# Arduino_BNO080.net
KiCad netlist of a schematic drawn in EAGLE
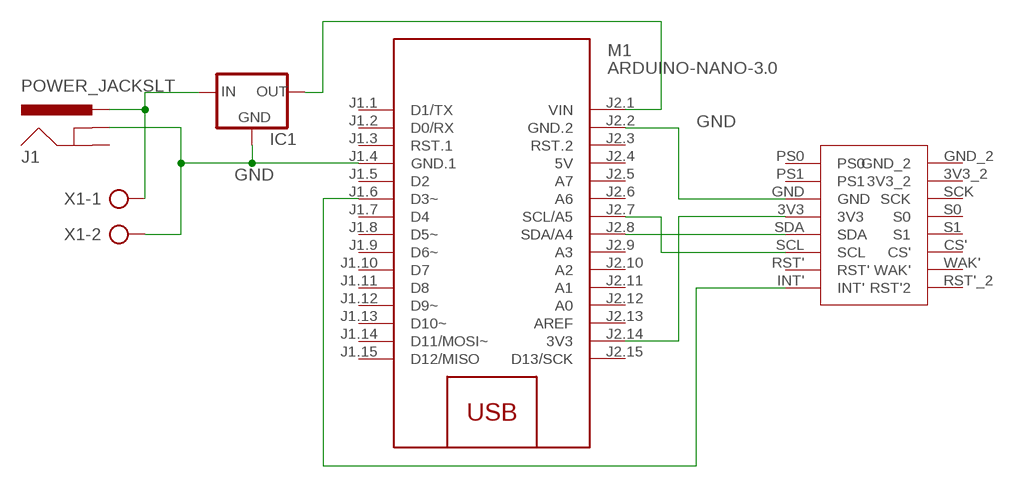
[diagram p0: schematic, sheet 1]

(export (version "E")
  (design (tool "Eeschema 10.0.6"))
  (components
    (comp (ref "IC1")
      (value "78XXS")
      (footprint "eagle-import:78XXS")
      (libsource (lib "eagle-import") (part "78XXS"))
    )
    (comp (ref "J1")
      (value "POWER_JACKSLT")
      (footprint "eagle-import:POWER_JACK_SLOT")
      (libsource (lib "eagle-import") (part "POWER_JACKSLT"))
    )
    (comp (ref "M1")
      (value "ARDUINO-NANO-3.0")
      (footprint "eagle-import:ARDUINO-NANO-3.0")
      (libsource (lib "eagle-import") (part "ARDUINO-NANO-3.0"))
    )
    (comp (ref "U$1")
      (value "BNO080")
      (footprint "eagle-import:BNO080")
      (libsource (lib "eagle-import") (part "BNO080"))
    )
    (comp (ref "X1")
      (value "AK300/2")
      (footprint "eagle-import:AK300_2")
      (libsource (lib "eagle-import") (part "AK300/2"))
    )
  )
  (nets
    (net (code "1") (name "/5V") (class "Default")
      (node (ref "M1") (pin "J2.4") (pinfunction "5V_J2.4") (pintype "power_in"))
    )
    (net (code "2") (name "/GND") (class "Default")
      (node (ref "IC1") (pin "GND") (pinfunction "GND_GND") (pintype "input"))
      (node (ref "J1") (pin "GND@1") (pinfunction "GNDBREAK_GND@1") (pintype "bidirectional"))
      (node (ref "M1") (pin "J1.4") (pinfunction "GND.1_J1.4") (pintype "power_in"))
      (node (ref "M1") (pin "J2.2") (pinfunction "GND.2_J2.2") (pintype "power_in"))
      (node (ref "U$1") (pin "GND") (pinfunction "GND_GND") (pintype "bidirectional"))
      (node (ref "X1") (pin "2") (pinfunction "KL_2") (pintype "passive"))
    )
    (net (code "3") (name "Net-(M1-3V3)") (class "Default")
      (node (ref "M1") (pin "J2.14") (pinfunction "3V3_J2.14") (pintype "power_in"))
      (node (ref "U$1") (pin "3V3") (pinfunction "3V3_3V3") (pintype "bidirectional"))
    )
    (net (code "4") (name "Net-(M1-D3~{})") (class "Default")
      (node (ref "M1") (pin "J1.6") (pinfunction "D3~{}_J1.6") (pintype "bidirectional"))
      (node (ref "U$1") (pin "INT'") (pinfunction "INT'_INT'") (pintype "bidirectional"))
    )
    (net (code "5") (name "Net-(M1-SCL{slash}A5)") (class "Default")
      (node (ref "M1") (pin "J2.7") (pinfunction "SCL/A5_J2.7") (pintype "bidirectional"))
      (node (ref "U$1") (pin "SCL") (pinfunction "SCL_SCL") (pintype "bidirectional"))
    )
    (net (code "6") (name "Net-(M1-SDA{slash}A4)") (class "Default")
      (node (ref "M1") (pin "J2.8") (pinfunction "SDA/A4_J2.8") (pintype "bidirectional"))
      (node (ref "U$1") (pin "SDA") (pinfunction "SDA_SDA") (pintype "bidirectional"))
    )
    (net (code "7") (name "Net-(M1-VIN)") (class "Default")
      (node (ref "IC1") (pin "OUT") (pinfunction "OUT_OUT") (pintype "passive"))
      (node (ref "M1") (pin "J2.1") (pinfunction "VIN_J2.1") (pintype "power_in"))
    )
    (net (code "8") (name "Net-(X1A-KL)") (class "Default")
      (node (ref "IC1") (pin "IN") (pinfunction "IN_IN") (pintype "input"))
      (node (ref "J1") (pin "PWR") (pinfunction "PWR_PWR") (pintype "bidirectional"))
      (node (ref "X1") (pin "1") (pinfunction "KL_1") (pintype "passive"))
    )
    (net (code "9") (name "unconnected-(J1-GND-PadGND@2)") (class "Default")
      (node (ref "J1") (pin "GND@2") (pinfunction "GND_GND@2") (pintype "bidirectional"))
    )
    (net (code "10") (name "unconnected-(M1-A0-PadJ2.12)") (class "Default")
      (node (ref "M1") (pin "J2.12") (pinfunction "A0_J2.12") (pintype "bidirectional"))
    )
    (net (code "11") (name "unconnected-(M1-A1-PadJ2.11)") (class "Default")
      (node (ref "M1") (pin "J2.11") (pinfunction "A1_J2.11") (pintype "bidirectional"))
    )
    (net (code "12") (name "unconnected-(M1-A2-PadJ2.10)") (class "Default")
      (node (ref "M1") (pin "J2.10") (pinfunction "A2_J2.10") (pintype "bidirectional"))
    )
    (net (code "13") (name "unconnected-(M1-A3-PadJ2.9)") (class "Default")
      (node (ref "M1") (pin "J2.9") (pinfunction "A3_J2.9") (pintype "bidirectional"))
    )
    (net (code "14") (name "unconnected-(M1-A6-PadJ2.6)") (class "Default")
      (node (ref "M1") (pin "J2.6") (pinfunction "A6_J2.6") (pintype "bidirectional"))
    )
    (net (code "15") (name "unconnected-(M1-A7-PadJ2.5)") (class "Default")
      (node (ref "M1") (pin "J2.5") (pinfunction "A7_J2.5") (pintype "bidirectional"))
    )
    (net (code "16") (name "unconnected-(M1-AREF-PadJ2.13)") (class "Default")
      (node (ref "M1") (pin "J2.13") (pinfunction "AREF_J2.13") (pintype "bidirectional"))
    )
    (net (code "17") (name "unconnected-(M1-D0{slash}RX-PadJ1.2)") (class "Default")
      (node (ref "M1") (pin "J1.2") (pinfunction "D0/RX_J1.2") (pintype "bidirectional"))
    )
    (net (code "18") (name "unconnected-(M1-D1{slash}TX-PadJ1.1)") (class "Default")
      (node (ref "M1") (pin "J1.1") (pinfunction "D1/TX_J1.1") (pintype "bidirectional"))
    )
    (net (code "19") (name "unconnected-(M1-D2-PadJ1.5)") (class "Default")
      (node (ref "M1") (pin "J1.5") (pinfunction "D2_J1.5") (pintype "bidirectional"))
    )
    (net (code "20") (name "unconnected-(M1-D4-PadJ1.7)") (class "Default")
      (node (ref "M1") (pin "J1.7") (pinfunction "D4_J1.7") (pintype "bidirectional"))
    )
    (net (code "21") (name "unconnected-(M1-D5~{}-PadJ1.8)") (class "Default")
      (node (ref "M1") (pin "J1.8") (pinfunction "D5~{}_J1.8") (pintype "bidirectional"))
    )
    (net (code "22") (name "unconnected-(M1-D6~{}-PadJ1.9)") (class "Default")
      (node (ref "M1") (pin "J1.9") (pinfunction "D6~{}_J1.9") (pintype "bidirectional"))
    )
    (net (code "23") (name "unconnected-(M1-D7-PadJ1.10)") (class "Default")
      (node (ref "M1") (pin "J1.10") (pinfunction "D7_J1.10") (pintype "bidirectional"))
    )
    (net (code "24") (name "unconnected-(M1-D8-PadJ1.11)") (class "Default")
      (node (ref "M1") (pin "J1.11") (pinfunction "D8_J1.11") (pintype "bidirectional"))
    )
    (net (code "25") (name "unconnected-(M1-D9~{}-PadJ1.12)") (class "Default")
      (node (ref "M1") (pin "J1.12") (pinfunction "D9~{}_J1.12") (pintype "bidirectional"))
    )
    (net (code "26") (name "unconnected-(M1-D10~{}-PadJ1.13)") (class "Default")
      (node (ref "M1") (pin "J1.13") (pinfunction "D10~{}_J1.13") (pintype "bidirectional"))
    )
    (net (code "27") (name "unconnected-(M1-D11{slash}MOSI~{}-PadJ1.14)") (class "Default")
      (node (ref "M1") (pin "J1.14") (pinfunction "D11/MOSI~{}_J1.14") (pintype "bidirectional"))
    )
    (net (code "28") (name "unconnected-(M1-D12{slash}MISO-PadJ1.15)") (class "Default")
      (node (ref "M1") (pin "J1.15") (pinfunction "D12/MISO_J1.15") (pintype "bidirectional"))
    )
    (net (code "29") (name "unconnected-(M1-D13{slash}SCK-PadJ2.15)") (class "Default")
      (node (ref "M1") (pin "J2.15") (pinfunction "D13/SCK_J2.15") (pintype "bidirectional"))
    )
    (net (code "30") (name "unconnected-(M1-RST.1-PadJ1.3)") (class "Default")
      (node (ref "M1") (pin "J1.3") (pinfunction "RST.1_J1.3") (pintype "bidirectional"))
    )
    (net (code "31") (name "unconnected-(M1-RST.2-PadJ2.3)") (class "Default")
      (node (ref "M1") (pin "J2.3") (pinfunction "RST.2_J2.3") (pintype "bidirectional"))
    )
    (net (code "32") (name "unconnected-(U$1-Pad3V3_2)") (class "Default")
      (node (ref "U$1") (pin "3V3_2") (pinfunction "3V3_2_3V3_2") (pintype "bidirectional"))
    )
    (net (code "33") (name "unconnected-(U$1-PadCS')") (class "Default")
      (node (ref "U$1") (pin "CS'") (pinfunction "CS'_CS'") (pintype "bidirectional"))
    )
    (net (code "34") (name "unconnected-(U$1-PadGND_2)") (class "Default")
      (node (ref "U$1") (pin "GND_2") (pinfunction "GND_2_GND_2") (pintype "bidirectional"))
    )
    (net (code "35") (name "unconnected-(U$1-PadPS0)") (class "Default")
      (node (ref "U$1") (pin "PS0") (pinfunction "PS0_PS0") (pintype "bidirectional"))
    )
    (net (code "36") (name "unconnected-(U$1-PadPS1)") (class "Default")
      (node (ref "U$1") (pin "PS1") (pinfunction "PS1_PS1") (pintype "bidirectional"))
    )
    (net (code "37") (name "unconnected-(U$1-PadRST')") (class "Default")
      (node (ref "U$1") (pin "RST'") (pinfunction "RST'_RST'") (pintype "bidirectional"))
    )
    (net (code "38") (name "unconnected-(U$1-PadS0)") (class "Default")
      (node (ref "U$1") (pin "S0") (pinfunction "S0_S0") (pintype "bidirectional"))
    )
    (net (code "39") (name "unconnected-(U$1-PadS1)") (class "Default")
      (node (ref "U$1") (pin "S1") (pinfunction "S1_S1") (pintype "bidirectional"))
    )
    (net (code "40") (name "unconnected-(U$1-PadSCK)") (class "Default")
      (node (ref "U$1") (pin "SCK") (pinfunction "SCK_SCK") (pintype "bidirectional"))
    )
    (net (code "41") (name "unconnected-(U$1-PadWAK')") (class "Default")
      (node (ref "U$1") (pin "WAK'") (pinfunction "WAK'_WAK'") (pintype "bidirectional"))
    )
    (net (code "42") (name "unconnected-(U$1-RST'2-PadRST'_2)") (class "Default")
      (node (ref "U$1") (pin "RST'_2") (pinfunction "RST'2_RST'_2") (pintype "bidirectional"))
    )
  )
)
